# 7segments.net
KiCad netlist of a schematic drawn in Altium Designer
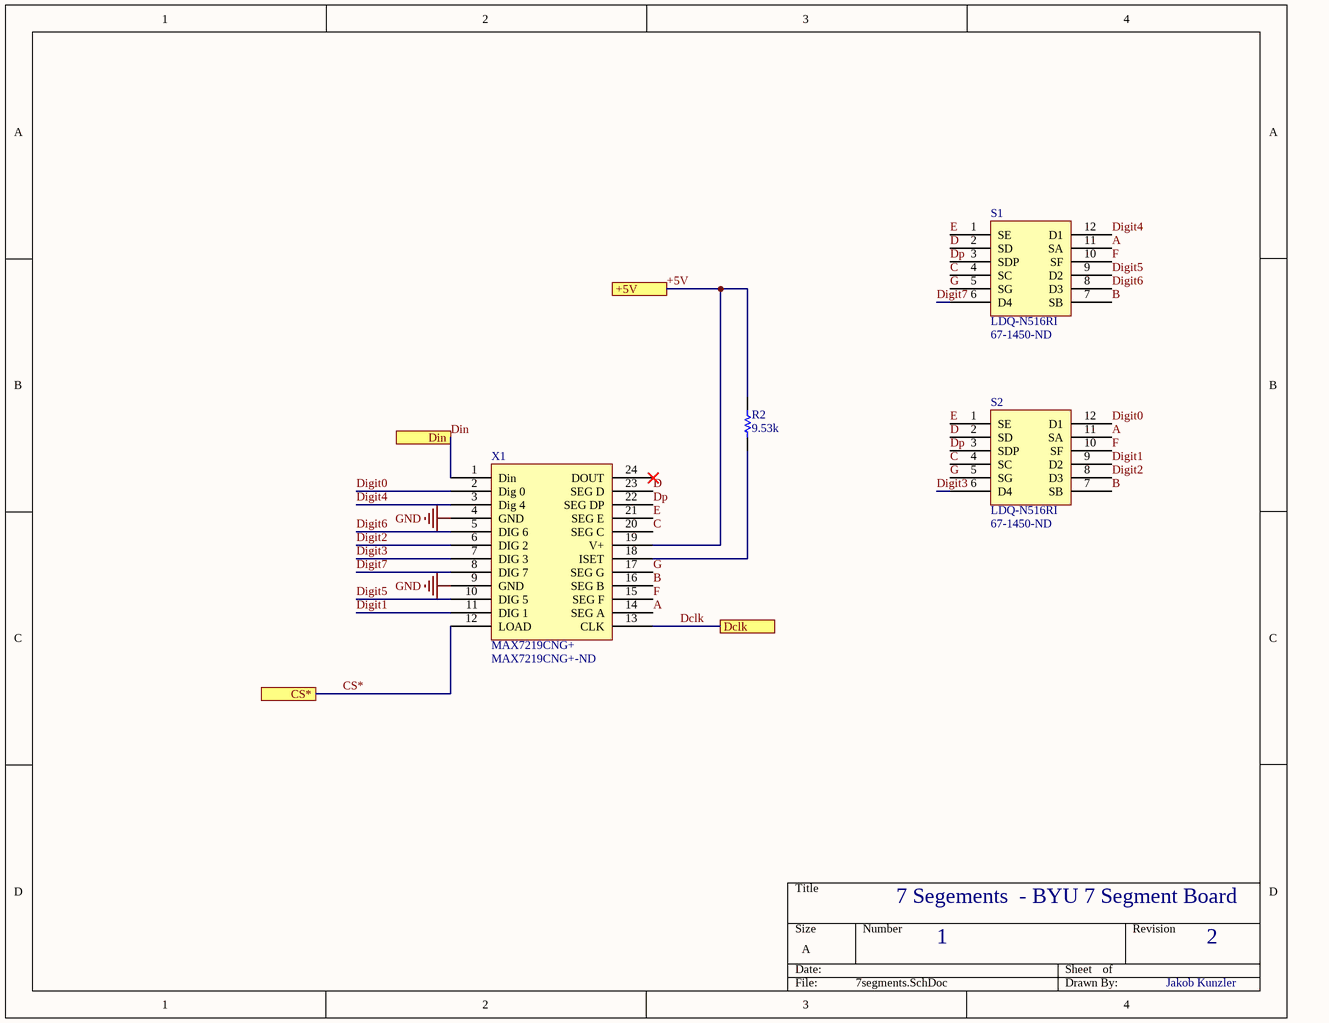
[diagram p0: 7segments.SchDoc]

(export (version "E")
  (design (tool "Eeschema 10.0.6"))
  (components
    (comp (ref "R2")
      (value "9.53k")
      (footprint "Resistor Through Hole")
      (description "MFR-25FBF52-9K53")
      (libsource (lib "BYU7SegBoard") (part "Resistor_9.53k"))
    )
    (comp (ref "S1")
      (value "LDQ-N516RI")
      (footprint "LDQ-516RI")
      (description "LED 7-SEG .56 QUAD S-RED CC MULT")
      (fields (field (name "SUPPLIER PART NUMBER 1") "67-1450-ND"))
      (libsource (lib "BYU7SegBoard") (part "SevenSegment"))
    )
    (comp (ref "S2")
      (value "LDQ-N516RI")
      (footprint "LDQ-516RI")
      (description "LED 7-SEG .56 QUAD S-RED CC MULT")
      (fields (field (name "SUPPLIER PART NUMBER 1") "67-1450-ND"))
      (libsource (lib "BYU7SegBoard") (part "SevenSegment"))
    )
    (comp (ref "X1")
      (value "MAX7219CNG+")
      (footprint "MAX7219")
      (description "Serially Interfaced, 8-Digit LED Display Driver")
      (fields (field (name "SUPPLIER PART NUMBER 1") "MAX7219CNG+-ND"))
      (libsource (lib "BYU7SegBoard") (part "MAX7219"))
    )
  )
  (nets
    (net (code "1") (name "/+5V") (class "Default")
      (node (ref "R2") (pin "2") (pinfunction "2_2") (pintype "passive"))
      (node (ref "X1") (pin "19") (pinfunction "V+_19") (pintype "passive"))
    )
    (net (code "2") (name "/A") (class "Default")
      (node (ref "S1") (pin "11") (pinfunction "SA_11") (pintype "passive"))
      (node (ref "S2") (pin "11") (pinfunction "SA_11") (pintype "passive"))
      (node (ref "X1") (pin "14") (pinfunction "SEG_A_14") (pintype "passive"))
    )
    (net (code "3") (name "/B") (class "Default")
      (node (ref "S1") (pin "7") (pinfunction "SB_7") (pintype "passive"))
      (node (ref "S2") (pin "7") (pinfunction "SB_7") (pintype "passive"))
      (node (ref "X1") (pin "16") (pinfunction "SEG_B_16") (pintype "passive"))
    )
    (net (code "4") (name "/C") (class "Default")
      (node (ref "S1") (pin "4") (pinfunction "SC_4") (pintype "passive"))
      (node (ref "S2") (pin "4") (pinfunction "SC_4") (pintype "passive"))
      (node (ref "X1") (pin "20") (pinfunction "SEG_C_20") (pintype "passive"))
    )
    (net (code "5") (name "/CS*") (class "Default")
      (node (ref "X1") (pin "12") (pinfunction "LOAD_12") (pintype "passive"))
    )
    (net (code "6") (name "/D") (class "Default")
      (node (ref "S1") (pin "2") (pinfunction "SD_2") (pintype "passive"))
      (node (ref "S2") (pin "2") (pinfunction "SD_2") (pintype "passive"))
      (node (ref "X1") (pin "23") (pinfunction "SEG_D_23") (pintype "passive"))
    )
    (net (code "7") (name "/Dclk") (class "Default")
      (node (ref "X1") (pin "13") (pinfunction "CLK_13") (pintype "passive"))
    )
    (net (code "8") (name "/Digit0") (class "Default")
      (node (ref "S2") (pin "12") (pinfunction "D1_12") (pintype "passive"))
      (node (ref "X1") (pin "2") (pinfunction "Dig_0_2") (pintype "passive"))
    )
    (net (code "9") (name "/Digit1") (class "Default")
      (node (ref "S2") (pin "9") (pinfunction "D2_9") (pintype "passive"))
      (node (ref "X1") (pin "11") (pinfunction "DIG_1_11") (pintype "passive"))
    )
    (net (code "10") (name "/Digit2") (class "Default")
      (node (ref "S2") (pin "8") (pinfunction "D3_8") (pintype "passive"))
      (node (ref "X1") (pin "6") (pinfunction "DIG_2_6") (pintype "passive"))
    )
    (net (code "11") (name "/Digit3") (class "Default")
      (node (ref "S2") (pin "6") (pinfunction "D4_6") (pintype "passive"))
      (node (ref "X1") (pin "7") (pinfunction "DIG_3_7") (pintype "passive"))
    )
    (net (code "12") (name "/Digit4") (class "Default")
      (node (ref "S1") (pin "12") (pinfunction "D1_12") (pintype "passive"))
      (node (ref "X1") (pin "3") (pinfunction "Dig_4_3") (pintype "passive"))
    )
    (net (code "13") (name "/Digit5") (class "Default")
      (node (ref "S1") (pin "9") (pinfunction "D2_9") (pintype "passive"))
      (node (ref "X1") (pin "10") (pinfunction "DIG_5_10") (pintype "passive"))
    )
    (net (code "14") (name "/Digit6") (class "Default")
      (node (ref "S1") (pin "8") (pinfunction "D3_8") (pintype "passive"))
      (node (ref "X1") (pin "5") (pinfunction "DIG_6_5") (pintype "passive"))
    )
    (net (code "15") (name "/Digit7") (class "Default")
      (node (ref "S1") (pin "6") (pinfunction "D4_6") (pintype "passive"))
      (node (ref "X1") (pin "8") (pinfunction "DIG_7_8") (pintype "passive"))
    )
    (net (code "16") (name "/Din") (class "Default")
      (node (ref "X1") (pin "1") (pinfunction "Din_1") (pintype "passive"))
    )
    (net (code "17") (name "/Dp") (class "Default")
      (node (ref "S1") (pin "3") (pinfunction "SDP_3") (pintype "passive"))
      (node (ref "S2") (pin "3") (pinfunction "SDP_3") (pintype "passive"))
      (node (ref "X1") (pin "22") (pinfunction "SEG_DP_22") (pintype "passive"))
    )
    (net (code "18") (name "/E") (class "Default")
      (node (ref "S1") (pin "1") (pinfunction "SE_1") (pintype "passive"))
      (node (ref "S2") (pin "1") (pinfunction "SE_1") (pintype "passive"))
      (node (ref "X1") (pin "21") (pinfunction "SEG_E_21") (pintype "passive"))
    )
    (net (code "19") (name "/F") (class "Default")
      (node (ref "S1") (pin "10") (pinfunction "SF_10") (pintype "passive"))
      (node (ref "S2") (pin "10") (pinfunction "SF_10") (pintype "passive"))
      (node (ref "X1") (pin "15") (pinfunction "SEG_F_15") (pintype "passive"))
    )
    (net (code "20") (name "/G") (class "Default")
      (node (ref "S1") (pin "5") (pinfunction "SG_5") (pintype "passive"))
      (node (ref "S2") (pin "5") (pinfunction "SG_5") (pintype "passive"))
      (node (ref "X1") (pin "17") (pinfunction "SEG_G_17") (pintype "passive"))
    )
    (net (code "21") (name "GND") (class "Default")
      (node (ref "X1") (pin "4") (pinfunction "GND_4") (pintype "passive"))
      (node (ref "X1") (pin "9") (pinfunction "GND_9") (pintype "passive"))
    )
    (net (code "22") (name "Net-(X1-ISET)") (class "Default")
      (node (ref "R2") (pin "1") (pinfunction "1_1") (pintype "passive"))
      (node (ref "X1") (pin "18") (pinfunction "ISET_18") (pintype "passive"))
    )
    (net (code "23") (name "unconnected-(X1-DOUT-Pad24)") (class "Default")
      (node (ref "X1") (pin "24") (pinfunction "DOUT_24") (pintype "passive+no_connect"))
    )
  )
)
